# AS3364_quad_mixer_0402_DIL-inv_v1_0.net
KiCad netlist of a schematic drawn in EAGLE
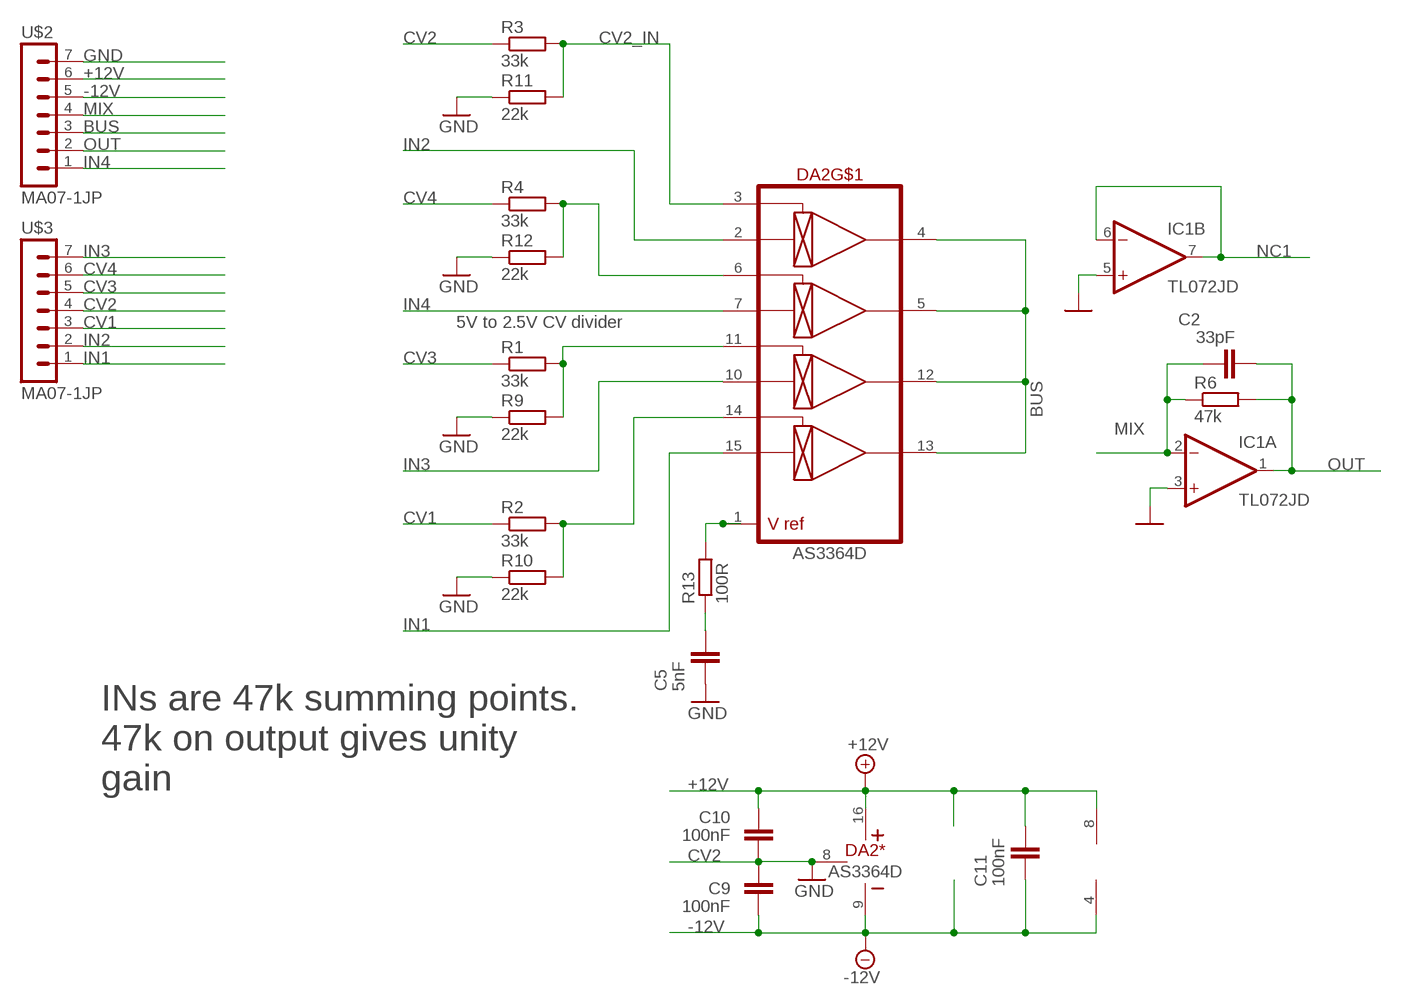
[diagram p0: schematic, sheet 1]

(export (version "E")
  (design (tool "Eeschema 10.0.6"))
  (components
    (comp (ref "C2")
      (value "33pF")
      (footprint "eagle-import:C0402")
      (libsource (lib "eagle-import") (part "C-EUC0402"))
    )
    (comp (ref "C5")
      (value "5nF")
      (footprint "eagle-import:C0402")
      (libsource (lib "eagle-import") (part "C-EUC0402"))
    )
    (comp (ref "C9")
      (value "100nF")
      (footprint "eagle-import:C0402")
      (libsource (lib "eagle-import") (part "C-EUC0402"))
    )
    (comp (ref "C10")
      (value "100nF")
      (footprint "eagle-import:C0402")
      (libsource (lib "eagle-import") (part "C-EUC0402"))
    )
    (comp (ref "C11")
      (value "100nF")
      (footprint "eagle-import:C0402")
      (libsource (lib "eagle-import") (part "C-EUC0402"))
    )
    (comp (ref "DA2")
      (value "AS3364D")
      (footprint "eagle-import:DIL16J")
      (libsource (lib "eagle-import") (part "AS3364D"))
    )
    (comp (ref "IC1")
      (value "TL072JD")
      (footprint "eagle-import:SO08J")
      (libsource (lib "eagle-import") (part "TL072JD"))
    )
    (comp (ref "R1")
      (value "33k")
      (footprint "eagle-import:R0402")
      (libsource (lib "eagle-import") (part "R-EU_R0402"))
    )
    (comp (ref "R2")
      (value "33k")
      (footprint "eagle-import:R0402")
      (libsource (lib "eagle-import") (part "R-EU_R0402"))
    )
    (comp (ref "R3")
      (value "33k")
      (footprint "eagle-import:R0402")
      (libsource (lib "eagle-import") (part "R-EU_R0402"))
    )
    (comp (ref "R4")
      (value "33k")
      (footprint "eagle-import:R0402")
      (libsource (lib "eagle-import") (part "R-EU_R0402"))
    )
    (comp (ref "R6")
      (value "47k")
      (footprint "eagle-import:R0402")
      (libsource (lib "eagle-import") (part "R-EU_R0402"))
    )
    (comp (ref "R9")
      (value "22k")
      (footprint "eagle-import:R0402")
      (libsource (lib "eagle-import") (part "R-EU_R0402"))
    )
    (comp (ref "R10")
      (value "22k")
      (footprint "eagle-import:R0402")
      (libsource (lib "eagle-import") (part "R-EU_R0402"))
    )
    (comp (ref "R11")
      (value "22k")
      (footprint "eagle-import:R0402")
      (libsource (lib "eagle-import") (part "R-EU_R0402"))
    )
    (comp (ref "R12")
      (value "22k")
      (footprint "eagle-import:R0402")
      (libsource (lib "eagle-import") (part "R-EU_R0402"))
    )
    (comp (ref "R13")
      (value "100R")
      (footprint "eagle-import:R0402")
      (libsource (lib "eagle-import") (part "R-EU_R0402"))
    )
    (comp (ref "U$2")
      (value "MA07-1JP")
      (footprint "eagle-import:SIP-PIN07-1J")
      (libsource (lib "eagle-import") (part "MA07-1JP"))
    )
    (comp (ref "U$3")
      (value "MA07-1JP")
      (footprint "eagle-import:SIP-PIN07-1J")
      (libsource (lib "eagle-import") (part "MA07-1JP"))
    )
  )
  (nets
    (net (code "1") (name "+12V") (class "Default")
      (node (ref "C10") (pin "2") (pinfunction "2_2") (pintype "passive"))
      (node (ref "C11") (pin "2") (pinfunction "2_2") (pintype "passive"))
      (node (ref "DA2") (pin "16") (pinfunction "V+_16") (pintype "power_in"))
      (node (ref "IC1") (pin "8") (pinfunction "V+_8") (pintype "power_in"))
      (node (ref "U$2") (pin "6") (pinfunction "6_6") (pintype "passive"))
    )
    (net (code "2") (name "-12V") (class "Default")
      (node (ref "C11") (pin "1") (pinfunction "1_1") (pintype "passive"))
      (node (ref "C9") (pin "1") (pinfunction "1_1") (pintype "passive"))
      (node (ref "DA2") (pin "9") (pinfunction "V-_9") (pintype "power_in"))
      (node (ref "IC1") (pin "4") (pinfunction "V-_4") (pintype "power_in"))
      (node (ref "U$2") (pin "5") (pinfunction "5_5") (pintype "passive"))
    )
    (net (code "3") (name "/BUS") (class "Default")
      (node (ref "DA2") (pin "12") (pinfunction "OUT3_12") (pintype "output"))
      (node (ref "DA2") (pin "13") (pinfunction "OUT4_13") (pintype "output"))
      (node (ref "DA2") (pin "4") (pinfunction "OUT1_4") (pintype "output"))
      (node (ref "DA2") (pin "5") (pinfunction "OUT2_5") (pintype "output"))
      (node (ref "U$2") (pin "3") (pinfunction "3_3") (pintype "passive"))
    )
    (net (code "4") (name "/CV1") (class "Default")
      (node (ref "R2") (pin "1") (pinfunction "1_1") (pintype "passive"))
      (node (ref "U$3") (pin "3") (pinfunction "3_3") (pintype "passive"))
    )
    (net (code "5") (name "/CV2") (class "Default")
      (node (ref "R3") (pin "1") (pinfunction "1_1") (pintype "passive"))
      (node (ref "U$3") (pin "4") (pinfunction "4_4") (pintype "passive"))
    )
    (net (code "6") (name "/CV2_IN") (class "Default")
      (node (ref "DA2") (pin "3") (pinfunction "CV1_3") (pintype "input"))
      (node (ref "R11") (pin "2") (pinfunction "2_2") (pintype "passive"))
      (node (ref "R3") (pin "2") (pinfunction "2_2") (pintype "passive"))
    )
    (net (code "7") (name "/CV3") (class "Default")
      (node (ref "R1") (pin "1") (pinfunction "1_1") (pintype "passive"))
      (node (ref "U$3") (pin "5") (pinfunction "5_5") (pintype "passive"))
    )
    (net (code "8") (name "/CV4") (class "Default")
      (node (ref "R4") (pin "1") (pinfunction "1_1") (pintype "passive"))
      (node (ref "U$3") (pin "6") (pinfunction "6_6") (pintype "passive"))
    )
    (net (code "9") (name "/IN1") (class "Default")
      (node (ref "DA2") (pin "15") (pinfunction "IN4_15") (pintype "input"))
      (node (ref "U$3") (pin "1") (pinfunction "1_1") (pintype "passive"))
    )
    (net (code "10") (name "/IN2") (class "Default")
      (node (ref "DA2") (pin "2") (pinfunction "IN1_2") (pintype "input"))
      (node (ref "U$3") (pin "2") (pinfunction "2_2") (pintype "passive"))
    )
    (net (code "11") (name "/IN3") (class "Default")
      (node (ref "DA2") (pin "10") (pinfunction "IN3_10") (pintype "input"))
      (node (ref "U$3") (pin "7") (pinfunction "7_7") (pintype "passive"))
    )
    (net (code "12") (name "/IN4") (class "Default")
      (node (ref "DA2") (pin "7") (pinfunction "IN2_7") (pintype "input"))
      (node (ref "U$2") (pin "1") (pinfunction "1_1") (pintype "passive"))
    )
    (net (code "13") (name "/MIX") (class "Default")
      (node (ref "C2") (pin "1") (pinfunction "1_1") (pintype "passive"))
      (node (ref "IC1") (pin "2") (pinfunction "-IN_2") (pintype "input"))
      (node (ref "R6") (pin "1") (pinfunction "1_1") (pintype "passive"))
      (node (ref "U$2") (pin "4") (pinfunction "4_4") (pintype "passive"))
    )
    (net (code "14") (name "/NC1") (class "Default")
      (node (ref "IC1") (pin "6") (pinfunction "-IN_6") (pintype "input"))
      (node (ref "IC1") (pin "7") (pinfunction "OUT_7") (pintype "output"))
    )
    (net (code "15") (name "/OUT") (class "Default")
      (node (ref "C2") (pin "2") (pinfunction "2_2") (pintype "passive"))
      (node (ref "IC1") (pin "1") (pinfunction "OUT_1") (pintype "output"))
      (node (ref "R6") (pin "2") (pinfunction "2_2") (pintype "passive"))
      (node (ref "U$2") (pin "2") (pinfunction "2_2") (pintype "passive"))
    )
    (net (code "16") (name "GND") (class "Default")
      (node (ref "C10") (pin "1") (pinfunction "1_1") (pintype "passive"))
      (node (ref "C5") (pin "1") (pinfunction "1_1") (pintype "passive"))
      (node (ref "C9") (pin "2") (pinfunction "2_2") (pintype "passive"))
      (node (ref "DA2") (pin "8") (pinfunction "GND_8") (pintype "power_in"))
      (node (ref "IC1") (pin "3") (pinfunction "+IN_3") (pintype "input"))
      (node (ref "IC1") (pin "5") (pinfunction "+IN_5") (pintype "input"))
      (node (ref "R10") (pin "1") (pinfunction "1_1") (pintype "passive"))
      (node (ref "R11") (pin "1") (pinfunction "1_1") (pintype "passive"))
      (node (ref "R12") (pin "1") (pinfunction "1_1") (pintype "passive"))
      (node (ref "R9") (pin "1") (pinfunction "1_1") (pintype "passive"))
      (node (ref "U$2") (pin "7") (pinfunction "7_7") (pintype "passive"))
    )
    (net (code "17") (name "Net-(C5-Pad2)") (class "Default")
      (node (ref "C5") (pin "2") (pinfunction "2_2") (pintype "passive"))
      (node (ref "R13") (pin "1") (pinfunction "1_1") (pintype "passive"))
    )
    (net (code "18") (name "Net-(DA2B-CV2)") (class "Default")
      (node (ref "DA2") (pin "6") (pinfunction "CV2_6") (pintype "input"))
      (node (ref "R12") (pin "2") (pinfunction "2_2") (pintype "passive"))
      (node (ref "R4") (pin "2") (pinfunction "2_2") (pintype "passive"))
    )
    (net (code "19") (name "Net-(DA2B-CV3)") (class "Default")
      (node (ref "DA2") (pin "11") (pinfunction "CV3_11") (pintype "input"))
      (node (ref "R1") (pin "2") (pinfunction "2_2") (pintype "passive"))
      (node (ref "R9") (pin "2") (pinfunction "2_2") (pintype "passive"))
    )
    (net (code "20") (name "Net-(DA2B-CV4)") (class "Default")
      (node (ref "DA2") (pin "14") (pinfunction "CV4_14") (pintype "input"))
      (node (ref "R10") (pin "2") (pinfunction "2_2") (pintype "passive"))
      (node (ref "R2") (pin "2") (pinfunction "2_2") (pintype "passive"))
    )
    (net (code "21") (name "Net-(DA2B-VREF)") (class "Default")
      (node (ref "DA2") (pin "1") (pinfunction "VREF_1") (pintype "output"))
      (node (ref "R13") (pin "2") (pinfunction "2_2") (pintype "passive"))
    )
  )
)
